# Adafruit_Flora_BLE_Friend.net
KiCad netlist of a schematic drawn in EAGLE
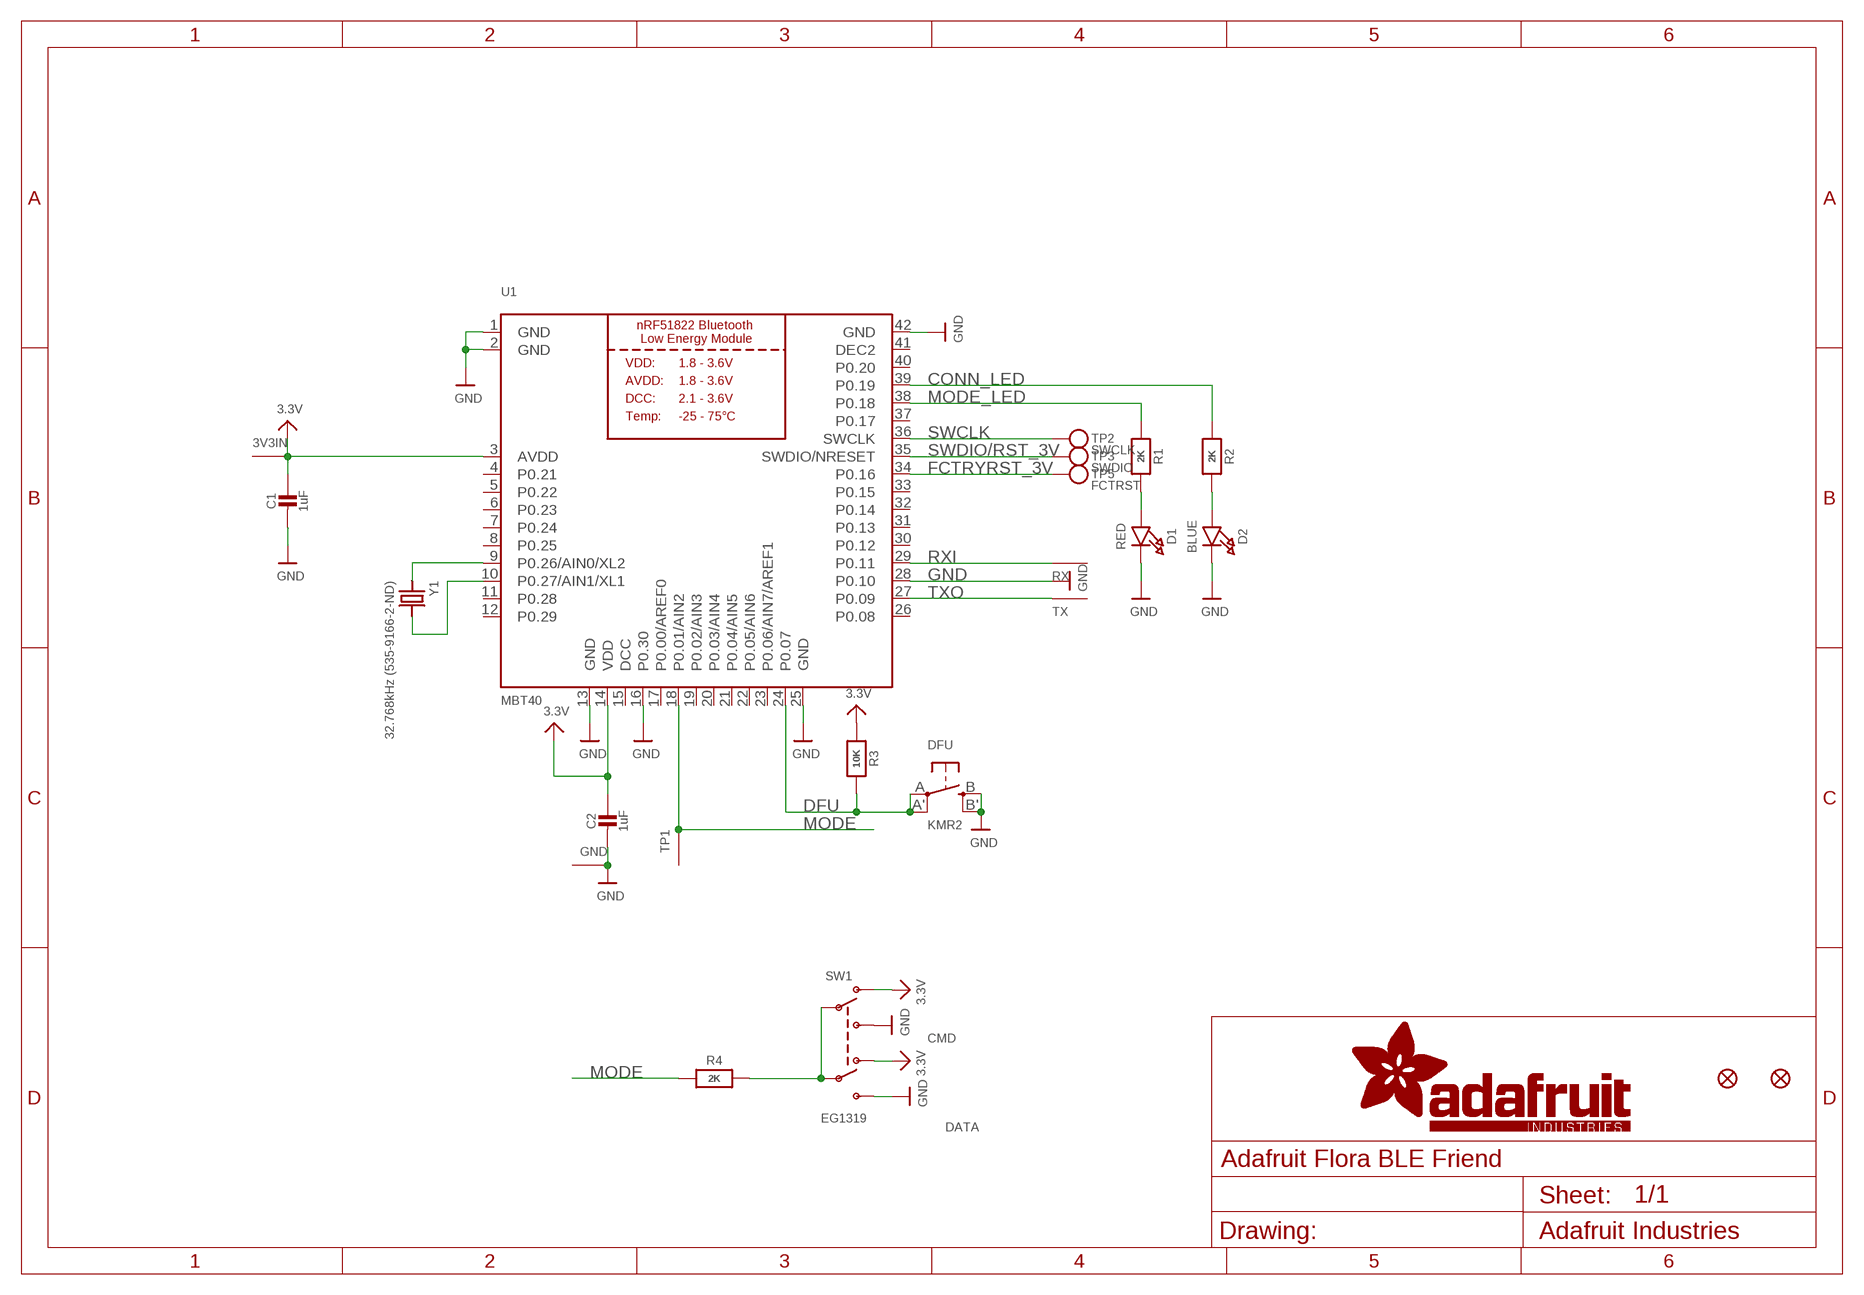
[diagram p0: schematic, sheet 1]

(export (version "E")
  (design (tool "Eeschema 10.0.6"))
  (components
    (comp (ref "3V3IN")
      (value "SEWTAP-2.0IN")
      (footprint "eagle-import:SEWINGTAP_2.0")
      (libsource (lib "eagle-import") (part "SEWTAP-2.0IN"))
    )
    (comp (ref "C1")
      (value "1uF")
      (footprint "eagle-import:0805-NO")
      (libsource (lib "eagle-import") (part "CAP_CERAMIC0805-NOOUTLINE"))
    )
    (comp (ref "C2")
      (value "1uF")
      (footprint "eagle-import:0805-NO")
      (libsource (lib "eagle-import") (part "CAP_CERAMIC0805-NOOUTLINE"))
    )
    (comp (ref "D1")
      (value "RED")
      (footprint "eagle-import:CHIPLED_0805_NOOUTLINE")
      (libsource (lib "eagle-import") (part "LED0805_NOOUTLINE"))
    )
    (comp (ref "D2")
      (value "BLUE")
      (footprint "eagle-import:CHIPLED_0805_NOOUTLINE")
      (libsource (lib "eagle-import") (part "LED0805_NOOUTLINE"))
    )
    (comp (ref "DFU")
      (value "KMR2")
      (footprint "eagle-import:BTN_KMR2_4.6X2.8")
      (libsource (lib "eagle-import") (part "SWITCH_TACT_SMT4.6X2.8"))
    )
    (comp (ref "FID1")
      (value "FIDUCIAL\"\"")
      (footprint "eagle-import:FIDUCIAL_1MM")
      (libsource (lib "eagle-import") (part "FIDUCIAL{dblquote}{dblquote}"))
    )
    (comp (ref "FID2")
      (value "FIDUCIAL\"\"")
      (footprint "eagle-import:FIDUCIAL_1MM")
      (libsource (lib "eagle-import") (part "FIDUCIAL{dblquote}{dblquote}"))
    )
    (comp (ref "GND")
      (value "SEWTAP-2.0IN")
      (footprint "eagle-import:SEWINGTAP_2.0")
      (libsource (lib "eagle-import") (part "SEWTAP-2.0IN"))
    )
    (comp (ref "R1")
      (value "2K")
      (footprint "eagle-import:0805-NO")
      (libsource (lib "eagle-import") (part "RESISTOR0805_NOOUTLINE"))
    )
    (comp (ref "R2")
      (value "2K")
      (footprint "eagle-import:0805-NO")
      (libsource (lib "eagle-import") (part "RESISTOR0805_NOOUTLINE"))
    )
    (comp (ref "R3")
      (value "10K")
      (footprint "eagle-import:0805-NO")
      (libsource (lib "eagle-import") (part "RESISTOR0805_NOOUTLINE"))
    )
    (comp (ref "R4")
      (value "2K")
      (footprint "eagle-import:0805-NO")
      (libsource (lib "eagle-import") (part "RESISTOR0805_NOOUTLINE"))
    )
    (comp (ref "RX")
      (value "SEWTAP-2.0IN")
      (footprint "eagle-import:SEWINGTAP_2.0")
      (libsource (lib "eagle-import") (part "SEWTAP-2.0IN"))
    )
    (comp (ref "SW1")
      (value "EG1319")
      (footprint "eagle-import:EG1390")
      (libsource (lib "eagle-import") (part "SWITCH_DPDTEG1390"))
    )
    (comp (ref "TP1")
      (value "SEWTAP-2.0IN")
      (footprint "eagle-import:SEWINGTAP_2.0")
      (libsource (lib "eagle-import") (part "SEWTAP-2.0IN"))
    )
    (comp (ref "TP2")
      (value "SWCLK")
      (footprint "eagle-import:PAD-1.5X2.0")
      (libsource (lib "eagle-import") (part "TESTPOINT1.5X2.0MM_NOCREAM"))
    )
    (comp (ref "TP3")
      (value "SWDIO")
      (footprint "eagle-import:PAD-1.5X2.0")
      (libsource (lib "eagle-import") (part "TESTPOINT1.5X2.0MM_NOCREAM"))
    )
    (comp (ref "TP5")
      (value "FCTRST")
      (footprint "eagle-import:PAD-1.5X2.0")
      (libsource (lib "eagle-import") (part "TESTPOINT1.5X2.0MM_NOCREAM"))
    )
    (comp (ref "TX")
      (value "SEWTAP-2.0IN")
      (footprint "eagle-import:SEWINGTAP_2.0")
      (libsource (lib "eagle-import") (part "SEWTAP-2.0IN"))
    )
    (comp (ref "U1")
      (value "MBT40")
      (footprint "eagle-import:BLE_MODULE_RAYTAC_MDBT40")
      (libsource (lib "eagle-import") (part "NRF51822_MODULE_MDBT40"))
    )
    (comp (ref "Y1")
      (value "32.768kHz (535-9166-2-ND)")
      (footprint "eagle-import:CRYSTAL_CYL_2X6MM_SMT")
      (libsource (lib "eagle-import") (part "CRYSTAL2.0X6.0_32.768"))
    )
  )
  (nets
    (net (code "1") (name "/CONN_LED") (class "Default")
      (node (ref "R2") (pin "1") (pinfunction "1_1") (pintype "passive"))
      (node (ref "U1") (pin "39") (pinfunction "P0.19_39") (pintype "bidirectional"))
    )
    (net (code "2") (name "/DCC") (class "Default")
      (node (ref "U1") (pin "15") (pinfunction "DCC_15") (pintype "power_in"))
    )
    (net (code "3") (name "/DEC2") (class "Default")
      (node (ref "U1") (pin "41") (pinfunction "DEC2_41") (pintype "power_in"))
    )
    (net (code "4") (name "/DFU") (class "Default")
      (node (ref "DFU") (pin "A") (pinfunction "P_A") (pintype "passive"))
      (node (ref "DFU") (pin "A'") (pinfunction "P1_A'") (pintype "passive"))
      (node (ref "R3") (pin "2") (pinfunction "2_2") (pintype "passive"))
      (node (ref "U1") (pin "24") (pinfunction "P0.07_24") (pintype "bidirectional"))
    )
    (net (code "5") (name "/FCTRYRST_3V") (class "Default")
      (node (ref "TP5") (pin "P$1") (pinfunction "P$1_P$1") (pintype "bidirectional"))
      (node (ref "U1") (pin "34") (pinfunction "P0.16_34") (pintype "bidirectional"))
    )
    (net (code "6") (name "/MODE") (class "Default")
      (node (ref "R4") (pin "1") (pinfunction "1_1") (pintype "passive"))
      (node (ref "TP1") (pin "P$1") (pinfunction "SEW_P$1") (pintype "bidirectional"))
      (node (ref "U1") (pin "18") (pinfunction "P0.01/AIN2_18") (pintype "bidirectional"))
    )
    (net (code "7") (name "/MODE_LED") (class "Default")
      (node (ref "R1") (pin "1") (pinfunction "1_1") (pintype "passive"))
      (node (ref "U1") (pin "38") (pinfunction "P0.18_38") (pintype "bidirectional"))
    )
    (net (code "8") (name "/RXI") (class "Default")
      (node (ref "RX") (pin "P$1") (pinfunction "SEW_P$1") (pintype "bidirectional"))
      (node (ref "U1") (pin "29") (pinfunction "P0.11_29") (pintype "bidirectional"))
    )
    (net (code "9") (name "/SWCLK") (class "Default")
      (node (ref "TP2") (pin "P$1") (pinfunction "P$1_P$1") (pintype "bidirectional"))
      (node (ref "U1") (pin "36") (pinfunction "SWCLK_36") (pintype "bidirectional"))
    )
    (net (code "10") (name "/SWDIO{slash}RST_3V") (class "Default")
      (node (ref "TP3") (pin "P$1") (pinfunction "P$1_P$1") (pintype "bidirectional"))
      (node (ref "U1") (pin "35") (pinfunction "SWDIO/NRESET_35") (pintype "bidirectional"))
    )
    (net (code "11") (name "/TXO") (class "Default")
      (node (ref "TX") (pin "P$1") (pinfunction "SEW_P$1") (pintype "bidirectional"))
      (node (ref "U1") (pin "27") (pinfunction "P0.09_27") (pintype "bidirectional"))
    )
    (net (code "12") (name "3.3V") (class "Default")
      (node (ref "3V3IN") (pin "P$1") (pinfunction "SEW_P$1") (pintype "bidirectional"))
      (node (ref "C1") (pin "1") (pinfunction "1_1") (pintype "passive"))
      (node (ref "C2") (pin "1") (pinfunction "1_1") (pintype "passive"))
      (node (ref "R3") (pin "1") (pinfunction "1_1") (pintype "passive"))
      (node (ref "SW1") (pin "O1") (pinfunction "O1_O1") (pintype "passive"))
      (node (ref "SW1") (pin "O2") (pinfunction "O2_O2") (pintype "passive"))
      (node (ref "U1") (pin "14") (pinfunction "VDD_14") (pintype "power_in"))
      (node (ref "U1") (pin "3") (pinfunction "AVDD_3") (pintype "power_in"))
    )
    (net (code "13") (name "GND") (class "Default")
      (node (ref "C1") (pin "2") (pinfunction "2_2") (pintype "passive"))
      (node (ref "C2") (pin "2") (pinfunction "2_2") (pintype "passive"))
      (node (ref "D1") (pin "C") (pinfunction "C_C") (pintype "passive"))
      (node (ref "D2") (pin "C") (pinfunction "C_C") (pintype "passive"))
      (node (ref "DFU") (pin "B") (pinfunction "S_B") (pintype "passive"))
      (node (ref "DFU") (pin "B'") (pinfunction "S1_B'") (pintype "passive"))
      (node (ref "GND") (pin "P$1") (pinfunction "SEW_P$1") (pintype "bidirectional"))
      (node (ref "SW1") (pin "S1") (pinfunction "S1_S1") (pintype "passive"))
      (node (ref "SW1") (pin "S2") (pinfunction "S2_S2") (pintype "passive"))
      (node (ref "U1") (pin "1") (pinfunction "GND_1") (pintype "power_in"))
      (node (ref "U1") (pin "13") (pinfunction "GND_13") (pintype "power_in"))
      (node (ref "U1") (pin "16") (pinfunction "P0.30_16") (pintype "bidirectional"))
      (node (ref "U1") (pin "2") (pinfunction "GND_2") (pintype "power_in"))
      (node (ref "U1") (pin "25") (pinfunction "GND_25") (pintype "power_in"))
      (node (ref "U1") (pin "28") (pinfunction "P0.10_28") (pintype "bidirectional"))
      (node (ref "U1") (pin "42") (pinfunction "GND_42") (pintype "power_in"))
    )
    (net (code "14") (name "Net-(D1-PadA)") (class "Default")
      (node (ref "D1") (pin "A") (pinfunction "A_A") (pintype "passive"))
      (node (ref "R1") (pin "2") (pinfunction "2_2") (pintype "passive"))
    )
    (net (code "15") (name "Net-(D2-PadA)") (class "Default")
      (node (ref "D2") (pin "A") (pinfunction "A_A") (pintype "passive"))
      (node (ref "R2") (pin "2") (pinfunction "2_2") (pintype "passive"))
    )
    (net (code "16") (name "Net-(R4-Pad2)") (class "Default")
      (node (ref "R4") (pin "2") (pinfunction "2_2") (pintype "passive"))
      (node (ref "SW1") (pin "P1") (pinfunction "P1_P1") (pintype "passive"))
      (node (ref "SW1") (pin "P2") (pinfunction "P2_P2") (pintype "passive"))
    )
    (net (code "17") (name "Net-(U1-P0.26{slash}AIN0{slash}XL2)") (class "Default")
      (node (ref "U1") (pin "9") (pinfunction "P0.26/AIN0/XL2_9") (pintype "bidirectional"))
      (node (ref "Y1") (pin "1") (pinfunction "1_1") (pintype "passive"))
    )
    (net (code "18") (name "Net-(U1-P0.27{slash}AIN1{slash}XL1)") (class "Default")
      (node (ref "U1") (pin "10") (pinfunction "P0.27/AIN1/XL1_10") (pintype "bidirectional"))
      (node (ref "Y1") (pin "2") (pinfunction "2_2") (pintype "passive"))
    )
    (net (code "19") (name "unconnected-(U1-P0.00{slash}AREF0-Pad17)") (class "Default")
      (node (ref "U1") (pin "17") (pinfunction "P0.00/AREF0_17") (pintype "bidirectional"))
    )
    (net (code "20") (name "unconnected-(U1-P0.02{slash}AIN3-Pad19)") (class "Default")
      (node (ref "U1") (pin "19") (pinfunction "P0.02/AIN3_19") (pintype "bidirectional"))
    )
    (net (code "21") (name "unconnected-(U1-P0.03{slash}AIN4-Pad20)") (class "Default")
      (node (ref "U1") (pin "20") (pinfunction "P0.03/AIN4_20") (pintype "bidirectional"))
    )
    (net (code "22") (name "unconnected-(U1-P0.04{slash}AIN5-Pad21)") (class "Default")
      (node (ref "U1") (pin "21") (pinfunction "P0.04/AIN5_21") (pintype "bidirectional"))
    )
    (net (code "23") (name "unconnected-(U1-P0.05{slash}AIN6-Pad22)") (class "Default")
      (node (ref "U1") (pin "22") (pinfunction "P0.05/AIN6_22") (pintype "bidirectional"))
    )
    (net (code "24") (name "unconnected-(U1-P0.06{slash}AIN7{slash}AREF1-Pad23)") (class "Default")
      (node (ref "U1") (pin "23") (pinfunction "P0.06/AIN7/AREF1_23") (pintype "bidirectional"))
    )
    (net (code "25") (name "unconnected-(U1-P0.08-Pad26)") (class "Default")
      (node (ref "U1") (pin "26") (pinfunction "P0.08_26") (pintype "bidirectional"))
    )
    (net (code "26") (name "unconnected-(U1-P0.12-Pad30)") (class "Default")
      (node (ref "U1") (pin "30") (pinfunction "P0.12_30") (pintype "bidirectional"))
    )
    (net (code "27") (name "unconnected-(U1-P0.13-Pad31)") (class "Default")
      (node (ref "U1") (pin "31") (pinfunction "P0.13_31") (pintype "bidirectional"))
    )
    (net (code "28") (name "unconnected-(U1-P0.14-Pad32)") (class "Default")
      (node (ref "U1") (pin "32") (pinfunction "P0.14_32") (pintype "bidirectional"))
    )
    (net (code "29") (name "unconnected-(U1-P0.15-Pad33)") (class "Default")
      (node (ref "U1") (pin "33") (pinfunction "P0.15_33") (pintype "bidirectional"))
    )
    (net (code "30") (name "unconnected-(U1-P0.17-Pad37)") (class "Default")
      (node (ref "U1") (pin "37") (pinfunction "P0.17_37") (pintype "bidirectional"))
    )
    (net (code "31") (name "unconnected-(U1-P0.20-Pad40)") (class "Default")
      (node (ref "U1") (pin "40") (pinfunction "P0.20_40") (pintype "bidirectional"))
    )
    (net (code "32") (name "unconnected-(U1-P0.21-Pad4)") (class "Default")
      (node (ref "U1") (pin "4") (pinfunction "P0.21_4") (pintype "bidirectional"))
    )
    (net (code "33") (name "unconnected-(U1-P0.22-Pad5)") (class "Default")
      (node (ref "U1") (pin "5") (pinfunction "P0.22_5") (pintype "bidirectional"))
    )
    (net (code "34") (name "unconnected-(U1-P0.23-Pad6)") (class "Default")
      (node (ref "U1") (pin "6") (pinfunction "P0.23_6") (pintype "bidirectional"))
    )
    (net (code "35") (name "unconnected-(U1-P0.24-Pad7)") (class "Default")
      (node (ref "U1") (pin "7") (pinfunction "P0.24_7") (pintype "bidirectional"))
    )
    (net (code "36") (name "unconnected-(U1-P0.25-Pad8)") (class "Default")
      (node (ref "U1") (pin "8") (pinfunction "P0.25_8") (pintype "bidirectional"))
    )
    (net (code "37") (name "unconnected-(U1-P0.28-Pad11)") (class "Default")
      (node (ref "U1") (pin "11") (pinfunction "P0.28_11") (pintype "bidirectional"))
    )
    (net (code "38") (name "unconnected-(U1-P0.29-Pad12)") (class "Default")
      (node (ref "U1") (pin "12") (pinfunction "P0.29_12") (pintype "bidirectional"))
    )
  )
)
